# led_cube.net
KiCad netlist of a schematic drawn in EAGLE
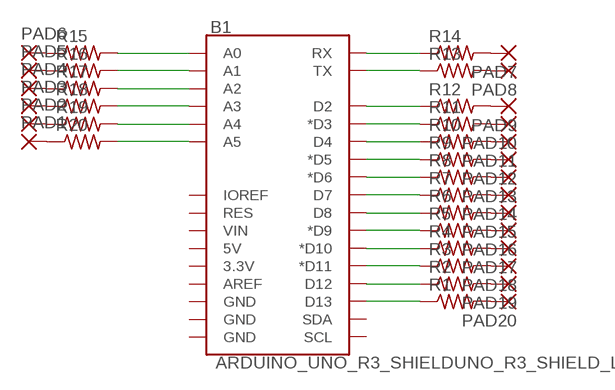
[diagram p0: schematic, sheet 1]

(export (version "E")
  (design (tool "Eeschema 10.0.6"))
  (components
    (comp (ref "B1")
      (value "ARDUINO_UNO_R3_SHIELDUNO_R3_SHIELD_LOCK")
      (footprint "eagle-import:UNO_R3_SHIELD_LOCK")
      (libsource (lib "eagle-import") (part "ARDUINO_UNO_R3_SHIELDUNO_R3_SHIELD_LOCK"))
    )
    (comp (ref "PAD1")
      (value "3,81/1,1")
      (footprint "eagle-import:3,81_1,1")
      (libsource (lib "eagle-import") (part "3,81/1,1"))
    )
    (comp (ref "PAD2")
      (value "3,81/1,1")
      (footprint "eagle-import:3,81_1,1")
      (libsource (lib "eagle-import") (part "3,81/1,1"))
    )
    (comp (ref "PAD3")
      (value "3,81/1,1")
      (footprint "eagle-import:3,81_1,1")
      (libsource (lib "eagle-import") (part "3,81/1,1"))
    )
    (comp (ref "PAD4")
      (value "3,81/1,1")
      (footprint "eagle-import:3,81_1,1")
      (libsource (lib "eagle-import") (part "3,81/1,1"))
    )
    (comp (ref "PAD5")
      (value "3,81/1,1")
      (footprint "eagle-import:3,81_1,1")
      (libsource (lib "eagle-import") (part "3,81/1,1"))
    )
    (comp (ref "PAD6")
      (value "3,81/1,1")
      (footprint "eagle-import:3,81_1,1")
      (libsource (lib "eagle-import") (part "3,81/1,1"))
    )
    (comp (ref "PAD7")
      (value "3,81/1,1")
      (footprint "eagle-import:3,81_1,1")
      (libsource (lib "eagle-import") (part "3,81/1,1"))
    )
    (comp (ref "PAD8")
      (value "3,81/1,1")
      (footprint "eagle-import:3,81_1,1")
      (libsource (lib "eagle-import") (part "3,81/1,1"))
    )
    (comp (ref "PAD9")
      (value "3,81/1,1")
      (footprint "eagle-import:3,81_1,1")
      (libsource (lib "eagle-import") (part "3,81/1,1"))
    )
    (comp (ref "PAD10")
      (value "3,81/1,1")
      (footprint "eagle-import:3,81_1,1")
      (libsource (lib "eagle-import") (part "3,81/1,1"))
    )
    (comp (ref "PAD11")
      (value "3,81/1,1")
      (footprint "eagle-import:3,81_1,1")
      (libsource (lib "eagle-import") (part "3,81/1,1"))
    )
    (comp (ref "PAD12")
      (value "3,81/1,1")
      (footprint "eagle-import:3,81_1,1")
      (libsource (lib "eagle-import") (part "3,81/1,1"))
    )
    (comp (ref "PAD13")
      (value "3,81/1,1")
      (footprint "eagle-import:3,81_1,1")
      (libsource (lib "eagle-import") (part "3,81/1,1"))
    )
    (comp (ref "PAD14")
      (value "3,81/1,1")
      (footprint "eagle-import:3,81_1,1")
      (libsource (lib "eagle-import") (part "3,81/1,1"))
    )
    (comp (ref "PAD15")
      (value "3,81/1,1")
      (footprint "eagle-import:3,81_1,1")
      (libsource (lib "eagle-import") (part "3,81/1,1"))
    )
    (comp (ref "PAD16")
      (value "3,81/1,1")
      (footprint "eagle-import:3,81_1,1")
      (libsource (lib "eagle-import") (part "3,81/1,1"))
    )
    (comp (ref "PAD17")
      (value "3,81/1,1")
      (footprint "eagle-import:3,81_1,1")
      (libsource (lib "eagle-import") (part "3,81/1,1"))
    )
    (comp (ref "PAD18")
      (value "3,81/1,1")
      (footprint "eagle-import:3,81_1,1")
      (libsource (lib "eagle-import") (part "3,81/1,1"))
    )
    (comp (ref "PAD19")
      (value "3,81/1,1")
      (footprint "eagle-import:3,81_1,1")
      (libsource (lib "eagle-import") (part "3,81/1,1"))
    )
    (comp (ref "PAD20")
      (value "3,81/1,1")
      (footprint "eagle-import:3,81_1,1")
      (libsource (lib "eagle-import") (part "3,81/1,1"))
    )
    (comp (ref "R1")
      (value "R-US_0204/7")
      (footprint "eagle-import:0204_7")
      (libsource (lib "eagle-import") (part "R-US_0204/7"))
    )
    (comp (ref "R2")
      (value "R-US_0204/7")
      (footprint "eagle-import:0204_7")
      (libsource (lib "eagle-import") (part "R-US_0204/7"))
    )
    (comp (ref "R3")
      (value "R-US_0204/7")
      (footprint "eagle-import:0204_7")
      (libsource (lib "eagle-import") (part "R-US_0204/7"))
    )
    (comp (ref "R4")
      (value "R-US_0204/7")
      (footprint "eagle-import:0204_7")
      (libsource (lib "eagle-import") (part "R-US_0204/7"))
    )
    (comp (ref "R5")
      (value "R-US_0204/7")
      (footprint "eagle-import:0204_7")
      (libsource (lib "eagle-import") (part "R-US_0204/7"))
    )
    (comp (ref "R6")
      (value "R-US_0204/7")
      (footprint "eagle-import:0204_7")
      (libsource (lib "eagle-import") (part "R-US_0204/7"))
    )
    (comp (ref "R7")
      (value "R-US_0204/7")
      (footprint "eagle-import:0204_7")
      (libsource (lib "eagle-import") (part "R-US_0204/7"))
    )
    (comp (ref "R8")
      (value "R-US_0204/7")
      (footprint "eagle-import:0204_7")
      (libsource (lib "eagle-import") (part "R-US_0204/7"))
    )
    (comp (ref "R9")
      (value "R-US_0204/7")
      (footprint "eagle-import:0204_7")
      (libsource (lib "eagle-import") (part "R-US_0204/7"))
    )
    (comp (ref "R10")
      (value "R-US_0204/7")
      (footprint "eagle-import:0204_7")
      (libsource (lib "eagle-import") (part "R-US_0204/7"))
    )
    (comp (ref "R11")
      (value "R-US_0204/7")
      (footprint "eagle-import:0204_7")
      (libsource (lib "eagle-import") (part "R-US_0204/7"))
    )
    (comp (ref "R12")
      (value "R-US_0204/7")
      (footprint "eagle-import:0204_7")
      (libsource (lib "eagle-import") (part "R-US_0204/7"))
    )
    (comp (ref "R13")
      (value "R-US_0204/7")
      (footprint "eagle-import:0204_7")
      (libsource (lib "eagle-import") (part "R-US_0204/7"))
    )
    (comp (ref "R14")
      (value "R-US_0204/7")
      (footprint "eagle-import:0204_7")
      (libsource (lib "eagle-import") (part "R-US_0204/7"))
    )
    (comp (ref "R15")
      (value "R-US_0204/7")
      (footprint "eagle-import:0204_7")
      (libsource (lib "eagle-import") (part "R-US_0204/7"))
    )
    (comp (ref "R16")
      (value "R-US_0204/7")
      (footprint "eagle-import:0204_7")
      (libsource (lib "eagle-import") (part "R-US_0204/7"))
    )
    (comp (ref "R17")
      (value "R-US_0204/7")
      (footprint "eagle-import:0204_7")
      (libsource (lib "eagle-import") (part "R-US_0204/7"))
    )
    (comp (ref "R18")
      (value "R-US_0204/7")
      (footprint "eagle-import:0204_7")
      (libsource (lib "eagle-import") (part "R-US_0204/7"))
    )
    (comp (ref "R19")
      (value "R-US_0204/7")
      (footprint "eagle-import:0204_7")
      (libsource (lib "eagle-import") (part "R-US_0204/7"))
    )
    (comp (ref "R20")
      (value "R-US_0204/7")
      (footprint "eagle-import:0204_7")
      (libsource (lib "eagle-import") (part "R-US_0204/7"))
    )
  )
  (nets
    (net (code "1") (name "Net-(B1-*D3)") (class "Default")
      (node (ref "B1") (pin "D3") (pinfunction "*D3_D3") (pintype "bidirectional"))
      (node (ref "R11") (pin "1") (pinfunction "1_1") (pintype "passive"))
    )
    (net (code "2") (name "Net-(B1-*D5)") (class "Default")
      (node (ref "B1") (pin "D5") (pinfunction "*D5_D5") (pintype "bidirectional"))
      (node (ref "R9") (pin "1") (pinfunction "1_1") (pintype "passive"))
    )
    (net (code "3") (name "Net-(B1-*D6)") (class "Default")
      (node (ref "B1") (pin "D6") (pinfunction "*D6_D6") (pintype "bidirectional"))
      (node (ref "R8") (pin "1") (pinfunction "1_1") (pintype "passive"))
    )
    (net (code "4") (name "Net-(B1-*D9)") (class "Default")
      (node (ref "B1") (pin "D9") (pinfunction "*D9_D9") (pintype "bidirectional"))
      (node (ref "R5") (pin "1") (pinfunction "1_1") (pintype "passive"))
    )
    (net (code "5") (name "Net-(B1-*D10)") (class "Default")
      (node (ref "B1") (pin "D10") (pinfunction "*D10_D10") (pintype "bidirectional"))
      (node (ref "R4") (pin "1") (pinfunction "1_1") (pintype "passive"))
    )
    (net (code "6") (name "Net-(B1-*D11)") (class "Default")
      (node (ref "B1") (pin "D11") (pinfunction "*D11_D11") (pintype "bidirectional"))
      (node (ref "R3") (pin "1") (pinfunction "1_1") (pintype "passive"))
    )
    (net (code "7") (name "Net-(B1-PadA0)") (class "Default")
      (node (ref "B1") (pin "A0") (pinfunction "A0_A0") (pintype "bidirectional"))
      (node (ref "R15") (pin "2") (pinfunction "2_2") (pintype "passive"))
    )
    (net (code "8") (name "Net-(B1-PadA1)") (class "Default")
      (node (ref "B1") (pin "A1") (pinfunction "A1_A1") (pintype "bidirectional"))
      (node (ref "R16") (pin "2") (pinfunction "2_2") (pintype "passive"))
    )
    (net (code "9") (name "Net-(B1-PadA2)") (class "Default")
      (node (ref "B1") (pin "A2") (pinfunction "A2_A2") (pintype "bidirectional"))
      (node (ref "R17") (pin "2") (pinfunction "2_2") (pintype "passive"))
    )
    (net (code "10") (name "Net-(B1-PadA3)") (class "Default")
      (node (ref "B1") (pin "A3") (pinfunction "A3_A3") (pintype "bidirectional"))
      (node (ref "R18") (pin "2") (pinfunction "2_2") (pintype "passive"))
    )
    (net (code "11") (name "Net-(B1-PadA4)") (class "Default")
      (node (ref "B1") (pin "A4") (pinfunction "A4_A4") (pintype "bidirectional"))
      (node (ref "R19") (pin "2") (pinfunction "2_2") (pintype "passive"))
    )
    (net (code "12") (name "Net-(B1-PadA5)") (class "Default")
      (node (ref "B1") (pin "A5") (pinfunction "A5_A5") (pintype "bidirectional"))
      (node (ref "R20") (pin "2") (pinfunction "2_2") (pintype "passive"))
    )
    (net (code "13") (name "Net-(B1-PadD2)") (class "Default")
      (node (ref "B1") (pin "D2") (pinfunction "D2_D2") (pintype "bidirectional"))
      (node (ref "R12") (pin "1") (pinfunction "1_1") (pintype "passive"))
    )
    (net (code "14") (name "Net-(B1-PadD4)") (class "Default")
      (node (ref "B1") (pin "D4") (pinfunction "D4_D4") (pintype "bidirectional"))
      (node (ref "R10") (pin "1") (pinfunction "1_1") (pintype "passive"))
    )
    (net (code "15") (name "Net-(B1-PadD7)") (class "Default")
      (node (ref "B1") (pin "D7") (pinfunction "D7_D7") (pintype "bidirectional"))
      (node (ref "R7") (pin "1") (pinfunction "1_1") (pintype "passive"))
    )
    (net (code "16") (name "Net-(B1-PadD8)") (class "Default")
      (node (ref "B1") (pin "D8") (pinfunction "D8_D8") (pintype "bidirectional"))
      (node (ref "R6") (pin "1") (pinfunction "1_1") (pintype "passive"))
    )
    (net (code "17") (name "Net-(B1-PadD12)") (class "Default")
      (node (ref "B1") (pin "D12") (pinfunction "D12_D12") (pintype "bidirectional"))
      (node (ref "R2") (pin "1") (pinfunction "1_1") (pintype "passive"))
    )
    (net (code "18") (name "Net-(B1-PadD13)") (class "Default")
      (node (ref "B1") (pin "D13") (pinfunction "D13_D13") (pintype "bidirectional"))
      (node (ref "R1") (pin "1") (pinfunction "1_1") (pintype "passive"))
    )
    (net (code "19") (name "Net-(B1-PadRX)") (class "Default")
      (node (ref "B1") (pin "RX") (pinfunction "RX_RX") (pintype "bidirectional"))
      (node (ref "R14") (pin "1") (pinfunction "1_1") (pintype "passive"))
    )
    (net (code "20") (name "Net-(B1-PadTX)") (class "Default")
      (node (ref "B1") (pin "TX") (pinfunction "TX_TX") (pintype "bidirectional"))
      (node (ref "R13") (pin "1") (pinfunction "1_1") (pintype "passive"))
    )
    (net (code "21") (name "Net-(PAD1-P)") (class "Default")
      (node (ref "PAD1") (pin "1") (pinfunction "P_1") (pintype "passive"))
      (node (ref "R20") (pin "1") (pinfunction "1_1") (pintype "passive"))
    )
    (net (code "22") (name "Net-(PAD2-P)") (class "Default")
      (node (ref "PAD2") (pin "1") (pinfunction "P_1") (pintype "passive"))
      (node (ref "R19") (pin "1") (pinfunction "1_1") (pintype "passive"))
    )
    (net (code "23") (name "Net-(PAD3-P)") (class "Default")
      (node (ref "PAD3") (pin "1") (pinfunction "P_1") (pintype "passive"))
      (node (ref "R18") (pin "1") (pinfunction "1_1") (pintype "passive"))
    )
    (net (code "24") (name "Net-(PAD4-P)") (class "Default")
      (node (ref "PAD4") (pin "1") (pinfunction "P_1") (pintype "passive"))
      (node (ref "R17") (pin "1") (pinfunction "1_1") (pintype "passive"))
    )
    (net (code "25") (name "Net-(PAD5-P)") (class "Default")
      (node (ref "PAD5") (pin "1") (pinfunction "P_1") (pintype "passive"))
      (node (ref "R16") (pin "1") (pinfunction "1_1") (pintype "passive"))
    )
    (net (code "26") (name "Net-(PAD6-P)") (class "Default")
      (node (ref "PAD6") (pin "1") (pinfunction "P_1") (pintype "passive"))
      (node (ref "R15") (pin "1") (pinfunction "1_1") (pintype "passive"))
    )
    (net (code "27") (name "Net-(PAD7-P)") (class "Default")
      (node (ref "PAD7") (pin "1") (pinfunction "P_1") (pintype "passive"))
      (node (ref "R14") (pin "2") (pinfunction "2_2") (pintype "passive"))
    )
    (net (code "28") (name "Net-(PAD8-P)") (class "Default")
      (node (ref "PAD8") (pin "1") (pinfunction "P_1") (pintype "passive"))
      (node (ref "R13") (pin "2") (pinfunction "2_2") (pintype "passive"))
    )
    (net (code "29") (name "Net-(PAD9-P)") (class "Default")
      (node (ref "PAD9") (pin "1") (pinfunction "P_1") (pintype "passive"))
      (node (ref "R12") (pin "2") (pinfunction "2_2") (pintype "passive"))
    )
    (net (code "30") (name "Net-(PAD10-P)") (class "Default")
      (node (ref "PAD10") (pin "1") (pinfunction "P_1") (pintype "passive"))
      (node (ref "R11") (pin "2") (pinfunction "2_2") (pintype "passive"))
    )
    (net (code "31") (name "Net-(PAD11-P)") (class "Default")
      (node (ref "PAD11") (pin "1") (pinfunction "P_1") (pintype "passive"))
      (node (ref "R10") (pin "2") (pinfunction "2_2") (pintype "passive"))
    )
    (net (code "32") (name "Net-(PAD12-P)") (class "Default")
      (node (ref "PAD12") (pin "1") (pinfunction "P_1") (pintype "passive"))
      (node (ref "R9") (pin "2") (pinfunction "2_2") (pintype "passive"))
    )
    (net (code "33") (name "Net-(PAD13-P)") (class "Default")
      (node (ref "PAD13") (pin "1") (pinfunction "P_1") (pintype "passive"))
      (node (ref "R8") (pin "2") (pinfunction "2_2") (pintype "passive"))
    )
    (net (code "34") (name "Net-(PAD14-P)") (class "Default")
      (node (ref "PAD14") (pin "1") (pinfunction "P_1") (pintype "passive"))
      (node (ref "R7") (pin "2") (pinfunction "2_2") (pintype "passive"))
    )
    (net (code "35") (name "Net-(PAD15-P)") (class "Default")
      (node (ref "PAD15") (pin "1") (pinfunction "P_1") (pintype "passive"))
      (node (ref "R6") (pin "2") (pinfunction "2_2") (pintype "passive"))
    )
    (net (code "36") (name "Net-(PAD16-P)") (class "Default")
      (node (ref "PAD16") (pin "1") (pinfunction "P_1") (pintype "passive"))
      (node (ref "R5") (pin "2") (pinfunction "2_2") (pintype "passive"))
    )
    (net (code "37") (name "Net-(PAD17-P)") (class "Default")
      (node (ref "PAD17") (pin "1") (pinfunction "P_1") (pintype "passive"))
      (node (ref "R4") (pin "2") (pinfunction "2_2") (pintype "passive"))
    )
    (net (code "38") (name "Net-(PAD18-P)") (class "Default")
      (node (ref "PAD18") (pin "1") (pinfunction "P_1") (pintype "passive"))
      (node (ref "R3") (pin "2") (pinfunction "2_2") (pintype "passive"))
    )
    (net (code "39") (name "Net-(PAD19-P)") (class "Default")
      (node (ref "PAD19") (pin "1") (pinfunction "P_1") (pintype "passive"))
      (node (ref "R2") (pin "2") (pinfunction "2_2") (pintype "passive"))
    )
    (net (code "40") (name "Net-(PAD20-P)") (class "Default")
      (node (ref "PAD20") (pin "1") (pinfunction "P_1") (pintype "passive"))
      (node (ref "R1") (pin "2") (pinfunction "2_2") (pintype "passive"))
    )
    (net (code "41") (name "unconnected-(B1-GND-PadGND@0)") (class "Default")
      (node (ref "B1") (pin "GND@0") (pinfunction "GND_GND@0") (pintype "bidirectional"))
    )
    (net (code "42") (name "unconnected-(B1-GND-PadGND@1)") (class "Default")
      (node (ref "B1") (pin "GND@1") (pinfunction "GND_GND@1") (pintype "bidirectional"))
    )
    (net (code "43") (name "unconnected-(B1-GND-PadGND@2)") (class "Default")
      (node (ref "B1") (pin "GND@2") (pinfunction "GND_GND@2") (pintype "bidirectional"))
    )
    (net (code "44") (name "unconnected-(B1-Pad3.3V)") (class "Default")
      (node (ref "B1") (pin "3.3V") (pinfunction "3.3V_3.3V") (pintype "bidirectional"))
    )
    (net (code "45") (name "unconnected-(B1-Pad5V)") (class "Default")
      (node (ref "B1") (pin "5V") (pinfunction "5V_5V") (pintype "bidirectional"))
    )
    (net (code "46") (name "unconnected-(B1-PadAREF)") (class "Default")
      (node (ref "B1") (pin "AREF") (pinfunction "AREF_AREF") (pintype "bidirectional"))
    )
    (net (code "47") (name "unconnected-(B1-PadIOREF)") (class "Default")
      (node (ref "B1") (pin "IOREF") (pinfunction "IOREF_IOREF") (pintype "bidirectional"))
    )
    (net (code "48") (name "unconnected-(B1-PadRES)") (class "Default")
      (node (ref "B1") (pin "RES") (pinfunction "RES_RES") (pintype "bidirectional"))
    )
    (net (code "49") (name "unconnected-(B1-PadSCL)") (class "Default")
      (node (ref "B1") (pin "SCL") (pinfunction "SCL_SCL") (pintype "bidirectional"))
    )
    (net (code "50") (name "unconnected-(B1-PadSDA)") (class "Default")
      (node (ref "B1") (pin "SDA") (pinfunction "SDA_SDA") (pintype "bidirectional"))
    )
    (net (code "51") (name "unconnected-(B1-PadVIN)") (class "Default")
      (node (ref "B1") (pin "VIN") (pinfunction "VIN_VIN") (pintype "bidirectional"))
    )
  )
)
